# AloyseTech-ELVN-RevA.net
KiCad netlist of a schematic drawn in EAGLE
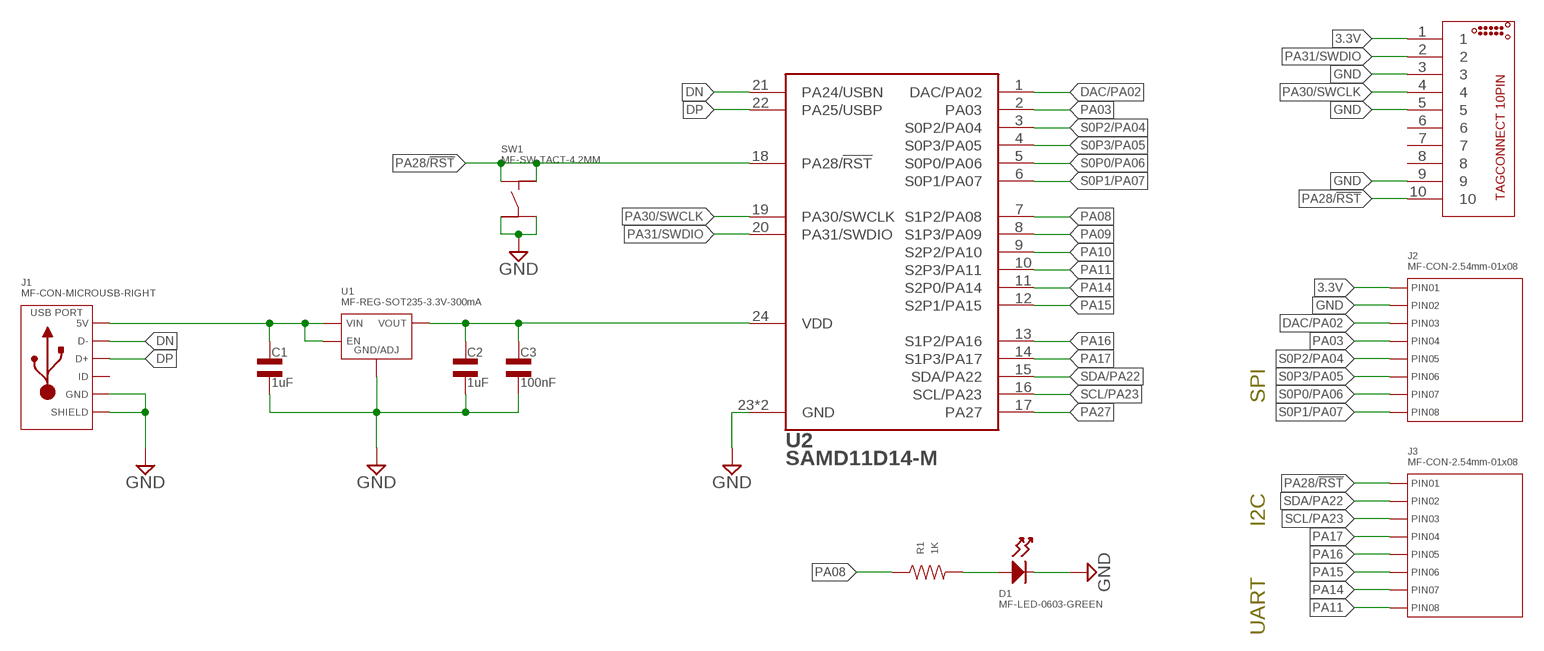
[diagram p0: schematic, sheet 1]

(export (version "E")
  (design (tool "Eeschema 10.0.6"))
  (components
    (comp (ref "C1")
      (value "1uF")
      (footprint "eagle-import:0805")
      (fields (field (name "TOLERANCE") "xx %") (field (name "VOLTAGE") "10V"))
      (libsource (lib "eagle-import") (part "CAPACITOR-NP-0805-COG-10V"))
    )
    (comp (ref "C2")
      (value "1uF")
      (footprint "eagle-import:0805")
      (fields (field (name "TOLERANCE") "xx %") (field (name "VOLTAGE") "10V"))
      (libsource (lib "eagle-import") (part "CAPACITOR-NP-0805-COG-10V"))
    )
    (comp (ref "C3")
      (value "100nF")
      (footprint "eagle-import:0402")
      (fields (field (name "TOLERANCE") "xx %") (field (name "VOLTAGE") "10V"))
      (libsource (lib "eagle-import") (part "CAPACITOR-NP-0402-COG-10V"))
    )
    (comp (ref "D1")
      (value "MF-LED-0603-GREEN")
      (footprint "eagle-import:LED0603")
      (fields (field (name "HOUSEPART") "YES"))
      (libsource (lib "eagle-import") (part "LED_SINGLE-0603-GREEN"))
    )
    (comp (ref "J1")
      (value "MF-CON-MICROUSB-RIGHT")
      (footprint "eagle-import:MICROUSB-RIGHT")
      (fields (field (name "HOUSEPART") "YES"))
      (libsource (lib "eagle-import") (part "USB_MICRO_RIGHT"))
    )
    (comp (ref "J2")
      (value "MF-CON-2.54mm-01x08")
      (footprint "eagle-import:PTH_2.54MM_01X08")
      (fields (field (name "HOUSEPART") "YES"))
      (libsource (lib "eagle-import") (part "CON_01X08_PTH_2.54MM"))
    )
    (comp (ref "J3")
      (value "MF-CON-2.54mm-01x08")
      (footprint "eagle-import:PTH_2.54MM_01X08")
      (fields (field (name "HOUSEPART") "YES"))
      (libsource (lib "eagle-import") (part "CON_01X08_PTH_2.54MM"))
    )
    (comp (ref "J4")
      (value "TC2050-COMBO-NC")
      (footprint "eagle-import:TC2050-10PIN1.27MM-COMBO-NC")
      (libsource (lib "eagle-import") (part "TC2050-COMBO-NC"))
    )
    (comp (ref "R1")
      (value "1K")
      (footprint "eagle-import:R0402")
      (libsource (lib "eagle-import") (part "RESISTOR_0402"))
    )
    (comp (ref "SW1")
      (value "MF-SW-TACT-4.2MM")
      (footprint "eagle-import:TACT4.2MM")
      (fields (field (name "HOUSEPART") "YES"))
      (libsource (lib "eagle-import") (part "TACT_4.2MM"))
    )
    (comp (ref "U1")
      (value "MF-REG-SOT235-3.3V-300mA")
      (footprint "eagle-import:SOT-23-5")
      (fields (field (name "HOUSEPART") "YES"))
      (libsource (lib "eagle-import") (part "TLV70233PDBVR"))
    )
    (comp (ref "U2")
      (value "SAMD11D14-M")
      (footprint "eagle-import:QFN50P400X400X90-25T275")
      (libsource (lib "eagle-import") (part "SAMD11D14-M"))
    )
  )
  (nets
    (net (code "1") (name "/PA28{slash}~{RST}") (class "Default")
      (node (ref "J3") (pin "P$1") (pinfunction "PIN1_P$1") (pintype "bidirectional"))
      (node (ref "J4") (pin "10") (pinfunction "10_10") (pintype "bidirectional"))
      (node (ref "SW1") (pin "P$1") (pinfunction "P$1_P$1") (pintype "bidirectional"))
      (node (ref "SW1") (pin "P$2") (pinfunction "P$2_P$2") (pintype "bidirectional"))
      (node (ref "U2") (pin "18") (pinfunction "PA28/~{RST}_18") (pintype "bidirectional"))
    )
    (net (code "2") (name "3.3V") (class "Default")
      (node (ref "C2") (pin "1") (pinfunction "1_1") (pintype "bidirectional"))
      (node (ref "C3") (pin "1") (pinfunction "1_1") (pintype "bidirectional"))
      (node (ref "J2") (pin "P$1") (pinfunction "PIN1_P$1") (pintype "bidirectional"))
      (node (ref "J4") (pin "1") (pinfunction "1_1") (pintype "bidirectional"))
      (node (ref "U1") (pin "P$5") (pinfunction "VOUT_P$5") (pintype "bidirectional"))
      (node (ref "U2") (pin "24") (pinfunction "VDD_24") (pintype "bidirectional"))
    )
    (net (code "3") (name "DAC{slash}PA02") (class "Default")
      (node (ref "J2") (pin "P$3") (pinfunction "PIN3_P$3") (pintype "bidirectional"))
      (node (ref "U2") (pin "1") (pinfunction "DAC/PA02_1") (pintype "bidirectional"))
    )
    (net (code "4") (name "DN") (class "Default")
      (node (ref "J1") (pin "2") (pinfunction "D-_2") (pintype "bidirectional"))
      (node (ref "U2") (pin "21") (pinfunction "PA24/USBN_21") (pintype "bidirectional"))
    )
    (net (code "5") (name "DP") (class "Default")
      (node (ref "J1") (pin "3") (pinfunction "D+_3") (pintype "bidirectional"))
      (node (ref "U2") (pin "22") (pinfunction "PA25/USBP_22") (pintype "bidirectional"))
    )
    (net (code "6") (name "GND") (class "Default")
      (node (ref "C1") (pin "2") (pinfunction "2_2") (pintype "bidirectional"))
      (node (ref "C2") (pin "2") (pinfunction "2_2") (pintype "bidirectional"))
      (node (ref "C3") (pin "2") (pinfunction "2_2") (pintype "bidirectional"))
      (node (ref "D1") (pin "CATHODE") (pinfunction "CATHODE_CATHODE") (pintype "power_in"))
      (node (ref "J1") (pin "5") (pinfunction "GND_5") (pintype "power_in"))
      (node (ref "J1") (pin "S1") (pinfunction "SLD_S1") (pintype "power_in"))
      (node (ref "J1") (pin "S2") (pinfunction "SLD_S2") (pintype "power_in"))
      (node (ref "J1") (pin "S3") (pinfunction "SLD_S3") (pintype "power_in"))
      (node (ref "J1") (pin "S4") (pinfunction "SLD_S4") (pintype "power_in"))
      (node (ref "J1") (pin "S5") (pinfunction "SLD_S5") (pintype "power_in"))
      (node (ref "J1") (pin "S6") (pinfunction "SLD_S6") (pintype "power_in"))
      (node (ref "J2") (pin "P$2") (pinfunction "PIN2_P$2") (pintype "bidirectional"))
      (node (ref "J4") (pin "3") (pinfunction "3_3") (pintype "bidirectional"))
      (node (ref "J4") (pin "5") (pinfunction "5_5") (pintype "bidirectional"))
      (node (ref "J4") (pin "9") (pinfunction "9_9") (pintype "bidirectional"))
      (node (ref "SW1") (pin "P$3") (pinfunction "P$3_P$3") (pintype "bidirectional"))
      (node (ref "SW1") (pin "P$4") (pinfunction "P$4_P$4") (pintype "bidirectional"))
      (node (ref "U1") (pin "P$2") (pinfunction "GND/ADJ_P$2") (pintype "bidirectional"))
      (node (ref "U2") (pin "23") (pinfunction "GND_23") (pintype "bidirectional"))
      (node (ref "U2") (pin "25") (pinfunction "GND_25") (pintype "bidirectional"))
    )
    (net (code "7") (name "Net-(D1-PadANODE)") (class "Default")
      (node (ref "D1") (pin "ANODE") (pinfunction "ANODE_ANODE") (pintype "power_in"))
      (node (ref "R1") (pin "P$2") (pinfunction "P$2_P$2") (pintype "passive"))
    )
    (net (code "8") (name "Net-(J1-5V)") (class "Default")
      (node (ref "C1") (pin "1") (pinfunction "1_1") (pintype "bidirectional"))
      (node (ref "J1") (pin "1") (pinfunction "5V_1") (pintype "power_in"))
      (node (ref "U1") (pin "P$1") (pinfunction "VIN_P$1") (pintype "bidirectional"))
      (node (ref "U1") (pin "P$3") (pinfunction "EN_P$3") (pintype "bidirectional"))
    )
    (net (code "9") (name "PA03") (class "Default")
      (node (ref "J2") (pin "P$4") (pinfunction "PIN4_P$4") (pintype "bidirectional"))
      (node (ref "U2") (pin "2") (pinfunction "PA03_2") (pintype "bidirectional"))
    )
    (net (code "10") (name "PA08") (class "Default")
      (node (ref "R1") (pin "P$1") (pinfunction "P$1_P$1") (pintype "passive"))
      (node (ref "U2") (pin "7") (pinfunction "S1P2/PA08_7") (pintype "bidirectional"))
    )
    (net (code "11") (name "PA09") (class "Default")
      (node (ref "U2") (pin "8") (pinfunction "S1P3/PA09_8") (pintype "bidirectional"))
    )
    (net (code "12") (name "PA10") (class "Default")
      (node (ref "U2") (pin "9") (pinfunction "S2P2/PA10_9") (pintype "bidirectional"))
    )
    (net (code "13") (name "PA11") (class "Default")
      (node (ref "J3") (pin "P$8") (pinfunction "PIN8_P$8") (pintype "bidirectional"))
      (node (ref "U2") (pin "10") (pinfunction "S2P3/PA11_10") (pintype "bidirectional"))
    )
    (net (code "14") (name "PA14") (class "Default")
      (node (ref "J3") (pin "P$7") (pinfunction "PIN7_P$7") (pintype "bidirectional"))
      (node (ref "U2") (pin "11") (pinfunction "S2P0/PA14_11") (pintype "bidirectional"))
    )
    (net (code "15") (name "PA15") (class "Default")
      (node (ref "J3") (pin "P$6") (pinfunction "PIN6_P$6") (pintype "bidirectional"))
      (node (ref "U2") (pin "12") (pinfunction "S2P1/PA15_12") (pintype "bidirectional"))
    )
    (net (code "16") (name "PA16") (class "Default")
      (node (ref "J3") (pin "P$5") (pinfunction "PIN5_P$5") (pintype "bidirectional"))
      (node (ref "U2") (pin "13") (pinfunction "S1P2/PA16_13") (pintype "bidirectional"))
    )
    (net (code "17") (name "PA17") (class "Default")
      (node (ref "J3") (pin "P$4") (pinfunction "PIN4_P$4") (pintype "bidirectional"))
      (node (ref "U2") (pin "14") (pinfunction "S1P3/PA17_14") (pintype "bidirectional"))
    )
    (net (code "18") (name "PA27") (class "Default")
      (node (ref "U2") (pin "17") (pinfunction "PA27_17") (pintype "bidirectional"))
    )
    (net (code "19") (name "PA30{slash}SWCLK") (class "Default")
      (node (ref "J4") (pin "4") (pinfunction "4_4") (pintype "bidirectional"))
      (node (ref "U2") (pin "19") (pinfunction "PA30/SWCLK_19") (pintype "bidirectional"))
    )
    (net (code "20") (name "PA31{slash}SWDIO") (class "Default")
      (node (ref "J4") (pin "2") (pinfunction "2_2") (pintype "bidirectional"))
      (node (ref "U2") (pin "20") (pinfunction "PA31/SWDIO_20") (pintype "bidirectional"))
    )
    (net (code "21") (name "S0P0{slash}PA06") (class "Default")
      (node (ref "J2") (pin "P$7") (pinfunction "PIN7_P$7") (pintype "bidirectional"))
      (node (ref "U2") (pin "5") (pinfunction "S0P0/PA06_5") (pintype "bidirectional"))
    )
    (net (code "22") (name "S0P1{slash}PA07") (class "Default")
      (node (ref "J2") (pin "P$8") (pinfunction "PIN8_P$8") (pintype "bidirectional"))
      (node (ref "U2") (pin "6") (pinfunction "S0P1/PA07_6") (pintype "bidirectional"))
    )
    (net (code "23") (name "S0P2{slash}PA04") (class "Default")
      (node (ref "J2") (pin "P$5") (pinfunction "PIN5_P$5") (pintype "bidirectional"))
      (node (ref "U2") (pin "3") (pinfunction "S0P2/PA04_3") (pintype "bidirectional"))
    )
    (net (code "24") (name "S0P3{slash}PA05") (class "Default")
      (node (ref "J2") (pin "P$6") (pinfunction "PIN6_P$6") (pintype "bidirectional"))
      (node (ref "U2") (pin "4") (pinfunction "S0P3/PA05_4") (pintype "bidirectional"))
    )
    (net (code "25") (name "SCL{slash}PA23") (class "Default")
      (node (ref "J3") (pin "P$3") (pinfunction "PIN3_P$3") (pintype "bidirectional"))
      (node (ref "U2") (pin "16") (pinfunction "SCL/PA23_16") (pintype "bidirectional"))
    )
    (net (code "26") (name "SDA{slash}PA22") (class "Default")
      (node (ref "J3") (pin "P$2") (pinfunction "PIN2_P$2") (pintype "bidirectional"))
      (node (ref "U2") (pin "15") (pinfunction "SDA/PA22_15") (pintype "bidirectional"))
    )
    (net (code "27") (name "unconnected-(J1-ID-Pad4)") (class "Default")
      (node (ref "J1") (pin "4") (pinfunction "ID_4") (pintype "bidirectional"))
    )
    (net (code "28") (name "unconnected-(J4-Pad6)") (class "Default")
      (node (ref "J4") (pin "6") (pinfunction "6_6") (pintype "bidirectional"))
    )
    (net (code "29") (name "unconnected-(J4-Pad7)") (class "Default")
      (node (ref "J4") (pin "7") (pinfunction "7_7") (pintype "bidirectional"))
    )
    (net (code "30") (name "unconnected-(J4-Pad8)") (class "Default")
      (node (ref "J4") (pin "8") (pinfunction "8_8") (pintype "bidirectional"))
    )
  )
)
